# ConfigurableDelayTimer.net
KiCad netlist of a schematic drawn in EAGLE
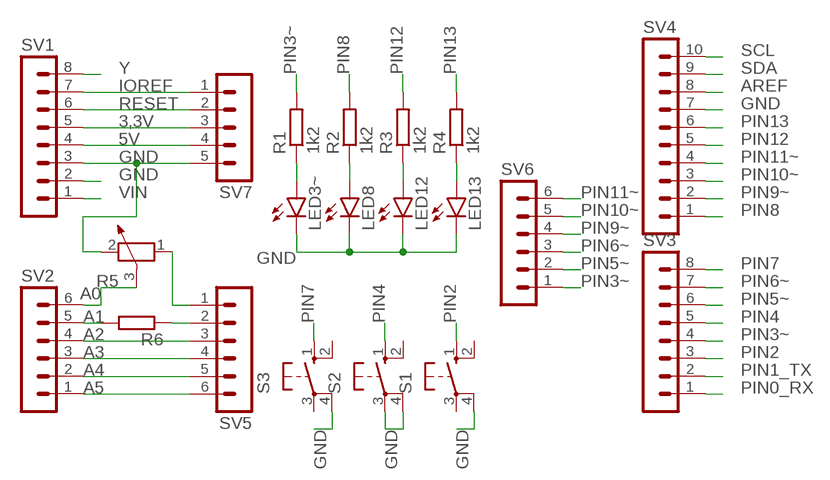
[diagram p0: schematic, sheet 1]

(export (version "E")
  (design (tool "Eeschema 10.0.6"))
  (components
    (comp (ref "LED3~")
      (value "LED5MM")
      (footprint "eagle-import:LED5MM")
      (libsource (lib "eagle-import") (part "LED5MM"))
    )
    (comp (ref "LED8")
      (value "LED5MM")
      (footprint "eagle-import:LED5MM")
      (libsource (lib "eagle-import") (part "LED5MM"))
    )
    (comp (ref "LED12")
      (value "LED5MM")
      (footprint "eagle-import:LED5MM")
      (libsource (lib "eagle-import") (part "LED5MM"))
    )
    (comp (ref "LED13")
      (value "LED5MM")
      (footprint "eagle-import:LED5MM")
      (libsource (lib "eagle-import") (part "LED5MM"))
    )
    (comp (ref "R1")
      (value "1k2")
      (footprint "eagle-import:0207_7")
      (libsource (lib "eagle-import") (part "R-EU_0207/7"))
    )
    (comp (ref "R2")
      (value "1k2")
      (footprint "eagle-import:0207_7")
      (libsource (lib "eagle-import") (part "R-EU_0207/7"))
    )
    (comp (ref "R3")
      (value "1k2")
      (footprint "eagle-import:0207_7")
      (libsource (lib "eagle-import") (part "R-EU_0207/7"))
    )
    (comp (ref "R4")
      (value "1k2")
      (footprint "eagle-import:0207_7")
      (libsource (lib "eagle-import") (part "R-EU_0207/7"))
    )
    (comp (ref "R5")
      (value "POTENTIOMETER_PT-10")
      (footprint "eagle-import:PT-10")
      (libsource (lib "eagle-import") (part "POTENTIOMETER_PT-10"))
    )
    (comp (ref "R6")
      (value "R-EU_0207/2V")
      (footprint "eagle-import:0207_2V")
      (libsource (lib "eagle-import") (part "R-EU_0207/2V"))
    )
    (comp (ref "S1")
      (value "40-XX")
      (footprint "eagle-import:B3F-40XX")
      (fields (field (name "MF") "OMRON COMPONENTS USA") (field (name "MPN") "B3F-4000"))
      (libsource (lib "eagle-import") (part "40-XX"))
    )
    (comp (ref "S2")
      (value "40-XX")
      (footprint "eagle-import:B3F-40XX")
      (fields (field (name "MF") "OMRON COMPONENTS USA") (field (name "MPN") "B3F-4000"))
      (libsource (lib "eagle-import") (part "40-XX"))
    )
    (comp (ref "S3")
      (value "40-XX")
      (footprint "eagle-import:B3F-40XX")
      (fields (field (name "MF") "OMRON COMPONENTS USA") (field (name "MPN") "B3F-4000"))
      (libsource (lib "eagle-import") (part "40-XX"))
    )
    (comp (ref "SV1")
      (value "MA08-1")
      (footprint "eagle-import:MA08-1")
      (libsource (lib "eagle-import") (part "MA08-1"))
    )
    (comp (ref "SV2")
      (value "MA06-1")
      (footprint "eagle-import:MA06-1")
      (libsource (lib "eagle-import") (part "MA06-1"))
    )
    (comp (ref "SV3")
      (value "MA08-1")
      (footprint "eagle-import:MA08-1")
      (libsource (lib "eagle-import") (part "MA08-1"))
    )
    (comp (ref "SV4")
      (value "MA10-1")
      (footprint "eagle-import:MA10-1")
      (libsource (lib "eagle-import") (part "MA10-1"))
    )
    (comp (ref "SV5")
      (value "MA06-1")
      (footprint "eagle-import:MA06-1")
      (libsource (lib "eagle-import") (part "MA06-1"))
    )
    (comp (ref "SV6")
      (value "MA06-1")
      (footprint "eagle-import:MA06-1")
      (libsource (lib "eagle-import") (part "MA06-1"))
    )
    (comp (ref "SV7")
      (value "MA05-1")
      (footprint "eagle-import:MA05-1")
      (libsource (lib "eagle-import") (part "MA05-1"))
    )
  )
  (nets
    (net (code "1") (name "/3,3V") (class "Default")
      (node (ref "SV1") (pin "5") (pinfunction "5_5") (pintype "passive"))
      (node (ref "SV7") (pin "3") (pinfunction "3_3") (pintype "passive"))
    )
    (net (code "2") (name "/5V") (class "Default")
      (node (ref "SV1") (pin "4") (pinfunction "4_4") (pintype "passive"))
      (node (ref "SV7") (pin "4") (pinfunction "4_4") (pintype "passive"))
    )
    (net (code "3") (name "/A0") (class "Default")
      (node (ref "R5") (pin "3") (pinfunction "3_3") (pintype "passive"))
      (node (ref "SV2") (pin "6") (pinfunction "6_6") (pintype "passive"))
    )
    (net (code "4") (name "/A1") (class "Default")
      (node (ref "R6") (pin "2") (pinfunction "2_2") (pintype "passive"))
      (node (ref "SV2") (pin "5") (pinfunction "5_5") (pintype "passive"))
    )
    (net (code "5") (name "/A2") (class "Default")
      (node (ref "SV2") (pin "4") (pinfunction "4_4") (pintype "passive"))
      (node (ref "SV5") (pin "3") (pinfunction "3_3") (pintype "passive"))
    )
    (net (code "6") (name "/A3") (class "Default")
      (node (ref "SV2") (pin "3") (pinfunction "3_3") (pintype "passive"))
      (node (ref "SV5") (pin "4") (pinfunction "4_4") (pintype "passive"))
    )
    (net (code "7") (name "/A4") (class "Default")
      (node (ref "SV2") (pin "2") (pinfunction "2_2") (pintype "passive"))
      (node (ref "SV5") (pin "5") (pinfunction "5_5") (pintype "passive"))
    )
    (net (code "8") (name "/A5") (class "Default")
      (node (ref "SV2") (pin "1") (pinfunction "1_1") (pintype "passive"))
      (node (ref "SV5") (pin "6") (pinfunction "6_6") (pintype "passive"))
    )
    (net (code "9") (name "/AREF") (class "Default")
      (node (ref "SV4") (pin "8") (pinfunction "8_8") (pintype "passive"))
    )
    (net (code "10") (name "/GND") (class "Default")
      (node (ref "LED12") (pin "K") (pinfunction "C_K") (pintype "passive"))
      (node (ref "LED13") (pin "K") (pinfunction "C_K") (pintype "passive"))
      (node (ref "LED3~") (pin "K") (pinfunction "C_K") (pintype "passive"))
      (node (ref "LED8") (pin "K") (pinfunction "C_K") (pintype "passive"))
      (node (ref "R5") (pin "2") (pinfunction "2_2") (pintype "passive"))
      (node (ref "S1") (pin "4") (pinfunction "P1_4") (pintype "passive"))
      (node (ref "S2") (pin "3") (pinfunction "P_3") (pintype "passive"))
      (node (ref "S2") (pin "4") (pinfunction "P1_4") (pintype "passive"))
      (node (ref "S3") (pin "4") (pinfunction "P1_4") (pintype "passive"))
      (node (ref "SV1") (pin "2") (pinfunction "2_2") (pintype "passive"))
      (node (ref "SV1") (pin "3") (pinfunction "3_3") (pintype "passive"))
      (node (ref "SV4") (pin "7") (pinfunction "7_7") (pintype "passive"))
      (node (ref "SV7") (pin "5") (pinfunction "5_5") (pintype "passive"))
    )
    (net (code "11") (name "/IOREF") (class "Default")
      (node (ref "SV1") (pin "7") (pinfunction "7_7") (pintype "passive"))
      (node (ref "SV7") (pin "1") (pinfunction "1_1") (pintype "passive"))
    )
    (net (code "12") (name "/PIN0_RX") (class "Default")
      (node (ref "SV3") (pin "1") (pinfunction "1_1") (pintype "passive"))
    )
    (net (code "13") (name "/PIN1_TX") (class "Default")
      (node (ref "SV3") (pin "2") (pinfunction "2_2") (pintype "passive"))
    )
    (net (code "14") (name "/PIN2") (class "Default")
      (node (ref "S1") (pin "1") (pinfunction "S_1") (pintype "passive"))
      (node (ref "SV3") (pin "3") (pinfunction "3_3") (pintype "passive"))
    )
    (net (code "15") (name "/PIN3~{}") (class "Default")
      (node (ref "R1") (pin "2") (pinfunction "2_2") (pintype "passive"))
      (node (ref "SV3") (pin "4") (pinfunction "4_4") (pintype "passive"))
      (node (ref "SV6") (pin "1") (pinfunction "1_1") (pintype "passive"))
    )
    (net (code "16") (name "/PIN4") (class "Default")
      (node (ref "S2") (pin "1") (pinfunction "S_1") (pintype "passive"))
      (node (ref "SV3") (pin "5") (pinfunction "5_5") (pintype "passive"))
    )
    (net (code "17") (name "/PIN5~{}") (class "Default")
      (node (ref "SV3") (pin "6") (pinfunction "6_6") (pintype "passive"))
      (node (ref "SV6") (pin "2") (pinfunction "2_2") (pintype "passive"))
    )
    (net (code "18") (name "/PIN6~{}") (class "Default")
      (node (ref "SV3") (pin "7") (pinfunction "7_7") (pintype "passive"))
      (node (ref "SV6") (pin "3") (pinfunction "3_3") (pintype "passive"))
    )
    (net (code "19") (name "/PIN7") (class "Default")
      (node (ref "S3") (pin "1") (pinfunction "S_1") (pintype "passive"))
      (node (ref "SV3") (pin "8") (pinfunction "8_8") (pintype "passive"))
    )
    (net (code "20") (name "/PIN8") (class "Default")
      (node (ref "R2") (pin "2") (pinfunction "2_2") (pintype "passive"))
      (node (ref "SV4") (pin "1") (pinfunction "1_1") (pintype "passive"))
    )
    (net (code "21") (name "/PIN9~{}") (class "Default")
      (node (ref "SV4") (pin "2") (pinfunction "2_2") (pintype "passive"))
      (node (ref "SV6") (pin "4") (pinfunction "4_4") (pintype "passive"))
    )
    (net (code "22") (name "/PIN10~{}") (class "Default")
      (node (ref "SV4") (pin "3") (pinfunction "3_3") (pintype "passive"))
      (node (ref "SV6") (pin "5") (pinfunction "5_5") (pintype "passive"))
    )
    (net (code "23") (name "/PIN11~{}") (class "Default")
      (node (ref "SV4") (pin "4") (pinfunction "4_4") (pintype "passive"))
      (node (ref "SV6") (pin "6") (pinfunction "6_6") (pintype "passive"))
    )
    (net (code "24") (name "/PIN12") (class "Default")
      (node (ref "R3") (pin "2") (pinfunction "2_2") (pintype "passive"))
      (node (ref "SV4") (pin "5") (pinfunction "5_5") (pintype "passive"))
    )
    (net (code "25") (name "/PIN13") (class "Default")
      (node (ref "R4") (pin "2") (pinfunction "2_2") (pintype "passive"))
      (node (ref "SV4") (pin "6") (pinfunction "6_6") (pintype "passive"))
    )
    (net (code "26") (name "/RESET") (class "Default")
      (node (ref "SV1") (pin "6") (pinfunction "6_6") (pintype "passive"))
      (node (ref "SV7") (pin "2") (pinfunction "2_2") (pintype "passive"))
    )
    (net (code "27") (name "/SCL") (class "Default")
      (node (ref "SV4") (pin "10") (pinfunction "10_10") (pintype "passive"))
    )
    (net (code "28") (name "/SDA") (class "Default")
      (node (ref "SV4") (pin "9") (pinfunction "9_9") (pintype "passive"))
    )
    (net (code "29") (name "/VIN") (class "Default")
      (node (ref "SV1") (pin "1") (pinfunction "1_1") (pintype "passive"))
    )
    (net (code "30") (name "/Y") (class "Default")
      (node (ref "SV1") (pin "8") (pinfunction "8_8") (pintype "passive"))
    )
    (net (code "31") (name "Net-(LED3~-PadA)") (class "Default")
      (node (ref "LED3~") (pin "A") (pinfunction "A_A") (pintype "passive"))
      (node (ref "R1") (pin "1") (pinfunction "1_1") (pintype "passive"))
    )
    (net (code "32") (name "Net-(LED8-PadA)") (class "Default")
      (node (ref "LED8") (pin "A") (pinfunction "A_A") (pintype "passive"))
      (node (ref "R2") (pin "1") (pinfunction "1_1") (pintype "passive"))
    )
    (net (code "33") (name "Net-(LED12-PadA)") (class "Default")
      (node (ref "LED12") (pin "A") (pinfunction "A_A") (pintype "passive"))
      (node (ref "R3") (pin "1") (pinfunction "1_1") (pintype "passive"))
    )
    (net (code "34") (name "Net-(LED13-PadA)") (class "Default")
      (node (ref "LED13") (pin "A") (pinfunction "A_A") (pintype "passive"))
      (node (ref "R4") (pin "1") (pinfunction "1_1") (pintype "passive"))
    )
    (net (code "35") (name "Net-(R5-Pad1)") (class "Default")
      (node (ref "R5") (pin "1") (pinfunction "1_1") (pintype "passive"))
      (node (ref "SV5") (pin "1") (pinfunction "1_1") (pintype "passive"))
    )
    (net (code "36") (name "Net-(R6-Pad1)") (class "Default")
      (node (ref "R6") (pin "1") (pinfunction "1_1") (pintype "passive"))
      (node (ref "SV5") (pin "2") (pinfunction "2_2") (pintype "passive"))
    )
    (net (code "37") (name "unconnected-(S1-P-Pad3)") (class "Default")
      (node (ref "S1") (pin "3") (pinfunction "P_3") (pintype "passive"))
    )
    (net (code "38") (name "unconnected-(S1-S1-Pad2)") (class "Default")
      (node (ref "S1") (pin "2") (pinfunction "S1_2") (pintype "passive"))
    )
    (net (code "39") (name "unconnected-(S2-S1-Pad2)") (class "Default")
      (node (ref "S2") (pin "2") (pinfunction "S1_2") (pintype "passive"))
    )
    (net (code "40") (name "unconnected-(S3-P-Pad3)") (class "Default")
      (node (ref "S3") (pin "3") (pinfunction "P_3") (pintype "passive"))
    )
    (net (code "41") (name "unconnected-(S3-S1-Pad2)") (class "Default")
      (node (ref "S3") (pin "2") (pinfunction "S1_2") (pintype "passive"))
    )
  )
)
